# SensorThing.net
KiCad netlist of a schematic drawn in Altium Designer
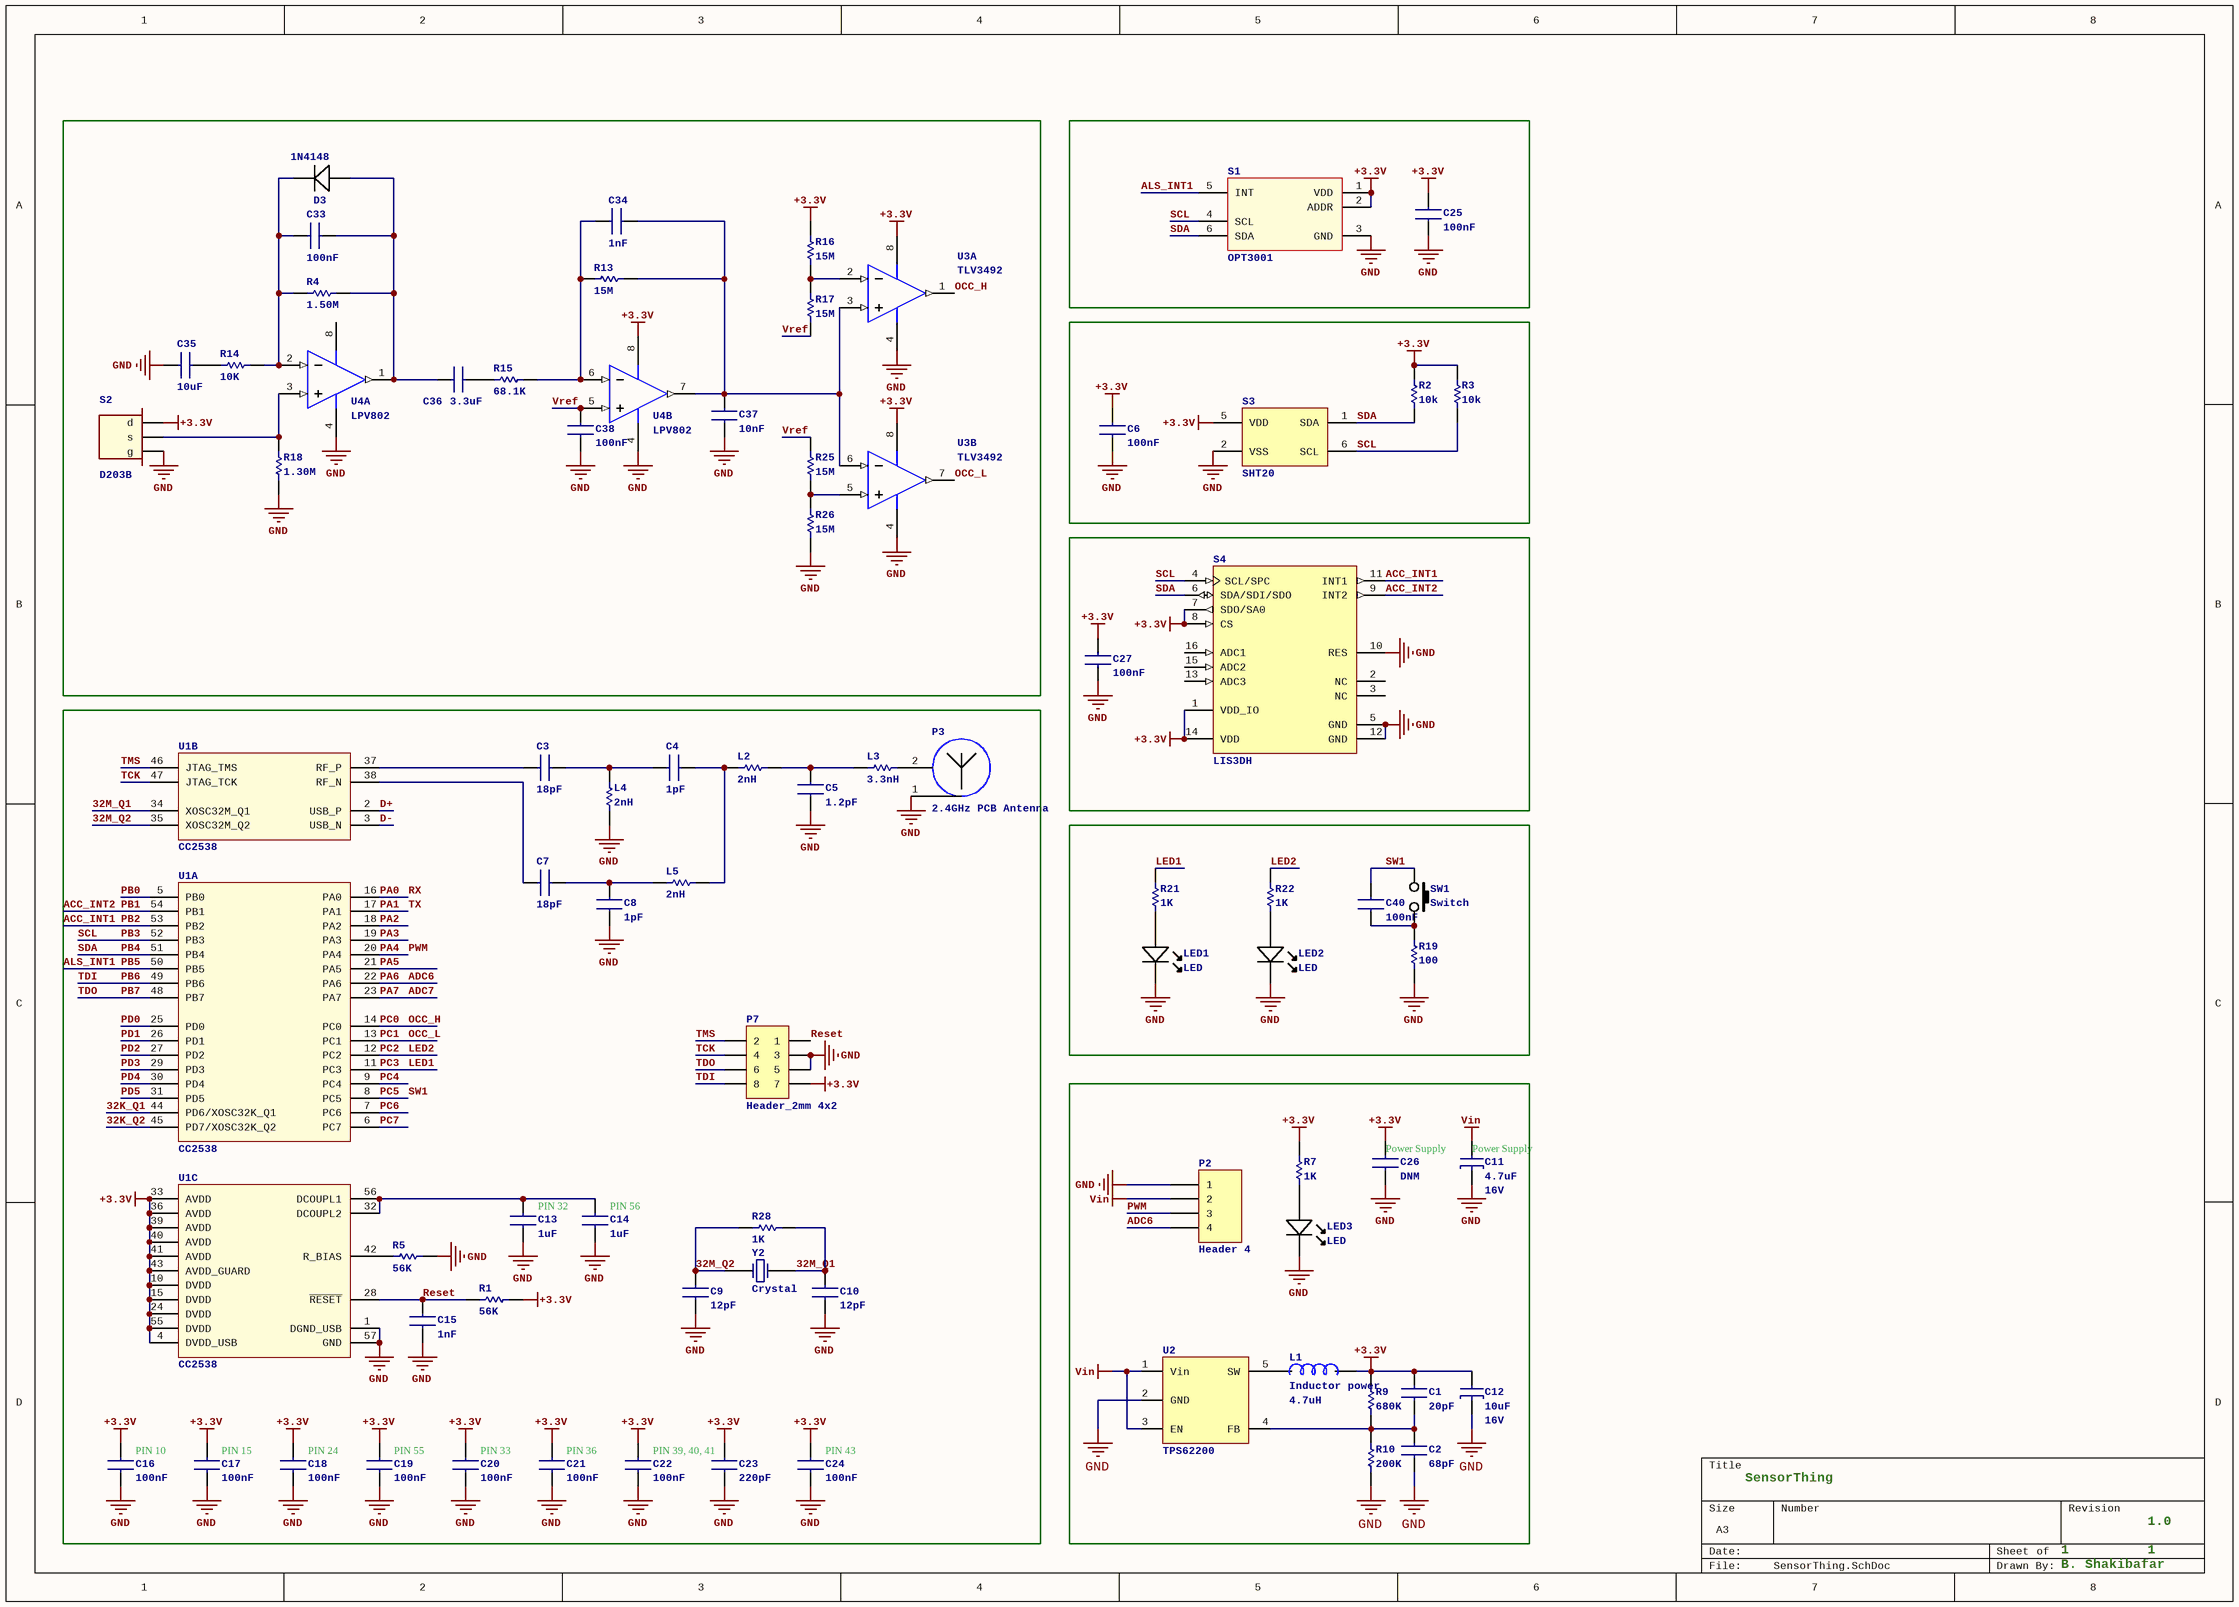
[diagram p0: SensorThing.SchDoc]

(export (version "E")
  (design (tool "Eeschema 10.0.6"))
  (components
    (comp (ref "C1")
      (value "Cap")
      (footprint "CAP 0603")
      (fields (field (name "VOLTAGE") "100V") (field (name "CAPACITY") "20pF"))
      (libsource (lib "Common") (part "Cap"))
    )
    (comp (ref "C2")
      (value "Cap")
      (footprint "CAP 0603")
      (fields (field (name "VOLTAGE") "100V") (field (name "CAPACITY") "68pF"))
      (libsource (lib "Common") (part "Cap"))
    )
    (comp (ref "C3")
      (value "Cap")
      (footprint "CAP 0603")
      (fields (field (name "VOLTAGE") "100V") (field (name "CAPACITY") "18pF"))
      (libsource (lib "Common") (part "Cap"))
    )
    (comp (ref "C4")
      (value "Cap")
      (footprint "CAP 0603")
      (fields (field (name "VOLTAGE") "100V") (field (name "CAPACITY") "1pF"))
      (libsource (lib "Common") (part "Cap"))
    )
    (comp (ref "C5")
      (value "Cap")
      (footprint "CAP 0603")
      (fields (field (name "VOLTAGE") "100V") (field (name "CAPACITY") "1.2pF"))
      (libsource (lib "Common") (part "Cap"))
    )
    (comp (ref "C6")
      (value "Cap")
      (footprint "CAP 0603")
      (fields (field (name "VOLTAGE") "100V") (field (name "CAPACITY") "100nF"))
      (libsource (lib "Common") (part "Cap"))
    )
    (comp (ref "C7")
      (value "Cap")
      (footprint "CAP 0603")
      (fields (field (name "VOLTAGE") "100V") (field (name "CAPACITY") "18pF"))
      (libsource (lib "Common") (part "Cap"))
    )
    (comp (ref "C8")
      (value "Cap")
      (footprint "CAP 0603")
      (fields (field (name "VOLTAGE") "100V") (field (name "CAPACITY") "1pF"))
      (libsource (lib "Common") (part "Cap"))
    )
    (comp (ref "C9")
      (value "Cap")
      (footprint "CAP 0603")
      (fields (field (name "VOLTAGE") "100V") (field (name "CAPACITY") "12pF"))
      (libsource (lib "Common") (part "Cap"))
    )
    (comp (ref "C10")
      (value "Cap")
      (footprint "CAP 0603")
      (fields (field (name "VOLTAGE") "100V") (field (name "CAPACITY") "12pF"))
      (libsource (lib "Common") (part "Cap"))
    )
    (comp (ref "C11")
      (value "Cap pol")
      (footprint "CAP A")
      (fields (field (name "CAPACITY") "4.7uF") (field (name "VOLTAGE") "16V"))
      (libsource (lib "Common") (part "Cap pol"))
    )
    (comp (ref "C12")
      (value "Cap pol")
      (footprint "CAP A")
      (fields (field (name "CAPACITY") "10uF") (field (name "VOLTAGE") "16V"))
      (libsource (lib "Common") (part "Cap pol"))
    )
    (comp (ref "C13")
      (value "Cap")
      (footprint "CAP 0603")
      (fields (field (name "VOLTAGE") "100V") (field (name "CAPACITY") "1uF"))
      (libsource (lib "Common") (part "Cap"))
    )
    (comp (ref "C14")
      (value "Cap")
      (footprint "CAP 0603")
      (fields (field (name "VOLTAGE") "100V") (field (name "CAPACITY") "1uF"))
      (libsource (lib "Common") (part "Cap"))
    )
    (comp (ref "C15")
      (value "Cap")
      (footprint "CAP 0603")
      (fields (field (name "VOLTAGE") "100V") (field (name "CAPACITY") "1nF"))
      (libsource (lib "Common") (part "Cap"))
    )
    (comp (ref "C16")
      (value "Cap")
      (footprint "CAP 0603")
      (fields (field (name "VOLTAGE") "100V") (field (name "CAPACITY") "100nF"))
      (libsource (lib "Common") (part "Cap"))
    )
    (comp (ref "C17")
      (value "Cap")
      (footprint "CAP 0603")
      (fields (field (name "VOLTAGE") "100V") (field (name "CAPACITY") "100nF"))
      (libsource (lib "Common") (part "Cap"))
    )
    (comp (ref "C18")
      (value "Cap")
      (footprint "CAP 0603")
      (fields (field (name "VOLTAGE") "100V") (field (name "CAPACITY") "100nF"))
      (libsource (lib "Common") (part "Cap"))
    )
    (comp (ref "C19")
      (value "Cap")
      (footprint "CAP 0603")
      (fields (field (name "VOLTAGE") "100V") (field (name "CAPACITY") "100nF"))
      (libsource (lib "Common") (part "Cap"))
    )
    (comp (ref "C20")
      (value "Cap")
      (footprint "CAP 0603")
      (fields (field (name "VOLTAGE") "100V") (field (name "CAPACITY") "100nF"))
      (libsource (lib "Common") (part "Cap"))
    )
    (comp (ref "C21")
      (value "Cap")
      (footprint "CAP 0603")
      (fields (field (name "VOLTAGE") "100V") (field (name "CAPACITY") "100nF"))
      (libsource (lib "Common") (part "Cap"))
    )
    (comp (ref "C22")
      (value "Cap")
      (footprint "CAP 0603")
      (fields (field (name "VOLTAGE") "100V") (field (name "CAPACITY") "100nF"))
      (libsource (lib "Common") (part "Cap"))
    )
    (comp (ref "C23")
      (value "Cap")
      (footprint "CAP 0603")
      (fields (field (name "VOLTAGE") "100V") (field (name "CAPACITY") "220pF"))
      (libsource (lib "Common") (part "Cap"))
    )
    (comp (ref "C24")
      (value "Cap")
      (footprint "CAP 0603")
      (fields (field (name "VOLTAGE") "100V") (field (name "CAPACITY") "100nF"))
      (libsource (lib "Common") (part "Cap"))
    )
    (comp (ref "C25")
      (value "Cap")
      (footprint "CAP 0603")
      (fields (field (name "VOLTAGE") "100V") (field (name "CAPACITY") "100nF"))
      (libsource (lib "Common") (part "Cap"))
    )
    (comp (ref "C26")
      (value "Cap")
      (footprint "CAP 0603")
      (fields (field (name "VOLTAGE") "100V") (field (name "CAPACITY") "DNM"))
      (libsource (lib "Common") (part "Cap"))
    )
    (comp (ref "C27")
      (value "Cap")
      (footprint "CAP 0603")
      (fields (field (name "VOLTAGE") "100V") (field (name "CAPACITY") "100nF"))
      (libsource (lib "Common") (part "Cap"))
    )
    (comp (ref "C33")
      (value "Cap")
      (footprint "CAP 0603")
      (fields (field (name "VOLTAGE") "100V") (field (name "CAPACITY") "100nF"))
      (libsource (lib "Common") (part "Cap"))
    )
    (comp (ref "C34")
      (value "Cap")
      (footprint "CAP 0603")
      (fields (field (name "VOLTAGE") "100V") (field (name "CAPACITY") "1nF"))
      (libsource (lib "Common") (part "Cap"))
    )
    (comp (ref "C35")
      (value "Cap")
      (footprint "CAP 0603")
      (fields (field (name "VOLTAGE") "100V") (field (name "CAPACITY") "10uF"))
      (libsource (lib "Common") (part "Cap"))
    )
    (comp (ref "C36")
      (value "Cap")
      (footprint "CAP 0603")
      (fields (field (name "VOLTAGE") "100V") (field (name "CAPACITY") "3.3uF"))
      (libsource (lib "Common") (part "Cap"))
    )
    (comp (ref "C37")
      (value "Cap")
      (footprint "CAP 0603")
      (fields (field (name "VOLTAGE") "100V") (field (name "CAPACITY") "10nF"))
      (libsource (lib "Common") (part "Cap"))
    )
    (comp (ref "C38")
      (value "Cap")
      (footprint "CAP 0603")
      (fields (field (name "VOLTAGE") "100V") (field (name "CAPACITY") "100nF"))
      (libsource (lib "Common") (part "Cap"))
    )
    (comp (ref "C40")
      (value "Cap")
      (footprint "CAP 0603")
      (fields (field (name "VOLTAGE") "100V") (field (name "CAPACITY") "100nF"))
      (libsource (lib "Common") (part "Cap"))
    )
    (comp (ref "D3") (value "1N4148") (footprint "SOD-523") (libsource (lib "Common") (part "Diode")))
    (comp (ref "L1")
      (value "Inductor power")
      (footprint "INDUCTOR 2520")
      (fields (field (name "ALTIUM_VALUE") "4.7uH"))
      (libsource (lib "Common") (part "Inductor power"))
    )
    (comp (ref "L2")
      (value "Res")
      (footprint "RES 0603")
      (description "Resistor")
      (fields (field (name "OHM") "2nH"))
      (libsource (lib "Common") (part "Res"))
    )
    (comp (ref "L3")
      (value "Res")
      (footprint "RES 0603")
      (description "Resistor")
      (fields (field (name "OHM") "3.3nH"))
      (libsource (lib "Common") (part "Res"))
    )
    (comp (ref "L4")
      (value "Res")
      (footprint "RES 0603")
      (description "Resistor")
      (fields (field (name "OHM") "2nH"))
      (libsource (lib "Common") (part "Res"))
    )
    (comp (ref "L5")
      (value "Res")
      (footprint "RES 0603")
      (description "Resistor")
      (fields (field (name "OHM") "2nH"))
      (libsource (lib "Common") (part "Res"))
    )
    (comp (ref "LED1")
      (value "LED")
      (footprint "LED 0603")
      (description "LED SMD")
      (libsource (lib "Common") (part "LED SMD"))
    )
    (comp (ref "LED2")
      (value "LED")
      (footprint "LED 0603")
      (description "LED SMD")
      (libsource (lib "Common") (part "LED SMD"))
    )
    (comp (ref "LED3")
      (value "LED")
      (footprint "LED 0603")
      (description "LED SMD")
      (libsource (lib "Common") (part "LED SMD"))
    )
    (comp (ref "P2")
      (value "Header 4")
      (footprint "HDR1X4")
      (description "Header, 4-Pin")
      (fields (field (name "PUBLISHER") "Altium Limited"))
      (libsource (lib "Miscellaneous Connectors") (part "Header 4"))
    )
    (comp (ref "P3")
      (value "2.4GHz PCB Antenna")
      (footprint "2.4 GHz Inverted F Antenna 1")
      (libsource (lib "My Lib") (part "2.4GHz PCB Antenna"))
    )
    (comp (ref "P7")
      (value "Header_2mm 4x2")
      (footprint "Header_2mm 4x2")
      (libsource (lib "Common") (part "Header_2mm 4x2"))
    )
    (comp (ref "R1")
      (value "Res")
      (footprint "RES 0603")
      (description "Resistor")
      (fields (field (name "OHM") "56K"))
      (libsource (lib "Common") (part "Res"))
    )
    (comp (ref "R2")
      (value "Res")
      (footprint "RES 0603")
      (description "Resistor")
      (fields (field (name "OHM") "10k"))
      (libsource (lib "Common") (part "Res"))
    )
    (comp (ref "R3")
      (value "Res")
      (footprint "RES 0603")
      (description "Resistor")
      (fields (field (name "OHM") "10k"))
      (libsource (lib "Common") (part "Res"))
    )
    (comp (ref "R4")
      (value "Res")
      (footprint "RES 0603")
      (description "Resistor")
      (fields (field (name "OHM") "1.50M"))
      (libsource (lib "Common") (part "Res"))
    )
    (comp (ref "R5")
      (value "Res")
      (footprint "RES 0603")
      (description "Resistor")
      (fields (field (name "OHM") "56K"))
      (libsource (lib "Common") (part "Res"))
    )
    (comp (ref "R7")
      (value "Res")
      (footprint "RES 0603")
      (description "Resistor")
      (fields (field (name "OHM") "1K"))
      (libsource (lib "Common") (part "Res"))
    )
    (comp (ref "R9")
      (value "Res")
      (footprint "RES 0603")
      (description "Resistor")
      (fields (field (name "OHM") "680K"))
      (libsource (lib "Common") (part "Res"))
    )
    (comp (ref "R10")
      (value "Res")
      (footprint "RES 0603")
      (description "Resistor")
      (fields (field (name "OHM") "200K"))
      (libsource (lib "Common") (part "Res"))
    )
    (comp (ref "R13")
      (value "Res")
      (footprint "RES 0603")
      (description "Resistor")
      (fields (field (name "OHM") "15M"))
      (libsource (lib "Common") (part "Res"))
    )
    (comp (ref "R14")
      (value "Res")
      (footprint "RES 0603")
      (description "Resistor")
      (fields (field (name "OHM") "10K"))
      (libsource (lib "Common") (part "Res"))
    )
    (comp (ref "R15")
      (value "Res")
      (footprint "RES 0603")
      (description "Resistor")
      (fields (field (name "OHM") "68.1K"))
      (libsource (lib "Common") (part "Res"))
    )
    (comp (ref "R16")
      (value "Res")
      (footprint "RES 0603")
      (description "Resistor")
      (fields (field (name "OHM") "15M"))
      (libsource (lib "Common") (part "Res"))
    )
    (comp (ref "R17")
      (value "Res")
      (footprint "RES 0603")
      (description "Resistor")
      (fields (field (name "OHM") "15M"))
      (libsource (lib "Common") (part "Res"))
    )
    (comp (ref "R18")
      (value "Res")
      (footprint "RES 0603")
      (description "Resistor")
      (fields (field (name "OHM") "1.30M"))
      (libsource (lib "Common") (part "Res"))
    )
    (comp (ref "R19")
      (value "Res")
      (footprint "RES 0603")
      (description "Resistor")
      (fields (field (name "OHM") "100"))
      (libsource (lib "Common") (part "Res"))
    )
    (comp (ref "R21")
      (value "Res")
      (footprint "RES 0603")
      (description "Resistor")
      (fields (field (name "OHM") "1K"))
      (libsource (lib "Common") (part "Res"))
    )
    (comp (ref "R22")
      (value "Res")
      (footprint "RES 0603")
      (description "Resistor")
      (fields (field (name "OHM") "1K"))
      (libsource (lib "Common") (part "Res"))
    )
    (comp (ref "R25")
      (value "Res")
      (footprint "RES 0603")
      (description "Resistor")
      (fields (field (name "OHM") "15M"))
      (libsource (lib "Common") (part "Res"))
    )
    (comp (ref "R26")
      (value "Res")
      (footprint "RES 0603")
      (description "Resistor")
      (fields (field (name "OHM") "15M"))
      (libsource (lib "Common") (part "Res"))
    )
    (comp (ref "R28")
      (value "Res")
      (footprint "RES 0603")
      (description "Resistor")
      (fields (field (name "OHM") "1K"))
      (libsource (lib "Common") (part "Res"))
    )
    (comp (ref "S1") (value "OPT3001") (footprint "USON-6pin") (libsource (lib "Chips") (part "OPT3001")))
    (comp (ref "S2") (value "D203B") (footprint "D203B") (libsource (lib "Common") (part "D203B PIR sensor")))
    (comp (ref "S3") (value "SHT20") (footprint "SHT20") (libsource (lib "My Lib") (part "SHT20")))
    (comp (ref "S4")
      (value "LIS3DH")
      (footprint "LGA16-3X3X1_N")
      (fields (field (name "MANUFACTURER") "STMicroelectronics"))
      (libsource (lib "STMicroelectronics Sensors & MEMS") (part "LIS3DH"))
    )
    (comp (ref "SW1")
      (value "Switch")
      (footprint "Switch Side-B3U")
      (description "micro Switch")
      (libsource (lib "Common") (part "Switch"))
    )
    (comp (ref "U1") (value "CC2538") (footprint "PVQFN56-CC2538") (libsource (lib "Chips") (part "CC2538")))
    (comp (ref "U2")
      (value "TPS62200")
      (footprint "SOT23-5")
      (description "NAND gate")
      (libsource (lib "My Lib") (part "TPS6220"))
    )
    (comp (ref "U3") (value "TLV3492") (footprint "VSSOP 8-Pin") (libsource (lib "My Lib") (part "TLV3492")))
    (comp (ref "U4") (value "LPV802") (footprint "VSSOP 8-Pin") (libsource (lib "My Lib") (part "LPV802")))
    (comp (ref "Y2") (value "Crystal") (footprint "Crystal 3225") (libsource (lib "Common") (part "Xtal")))
  )
  (nets
    (net (code "1") (name "+3.3V") (class "Default")
      (node (ref "C1") (pin "1") (pinfunction "1_1") (pintype "passive"))
      (node (ref "C12") (pin "1") (pinfunction "1_1") (pintype "passive"))
      (node (ref "C16") (pin "1") (pinfunction "1_1") (pintype "passive"))
      (node (ref "C17") (pin "1") (pinfunction "1_1") (pintype "passive"))
      (node (ref "C18") (pin "1") (pinfunction "1_1") (pintype "passive"))
      (node (ref "C19") (pin "1") (pinfunction "1_1") (pintype "passive"))
      (node (ref "C20") (pin "1") (pinfunction "1_1") (pintype "passive"))
      (node (ref "C21") (pin "1") (pinfunction "1_1") (pintype "passive"))
      (node (ref "C22") (pin "1") (pinfunction "1_1") (pintype "passive"))
      (node (ref "C23") (pin "1") (pinfunction "1_1") (pintype "passive"))
      (node (ref "C24") (pin "1") (pinfunction "1_1") (pintype "passive"))
      (node (ref "C25") (pin "1") (pinfunction "1_1") (pintype "passive"))
      (node (ref "C26") (pin "1") (pinfunction "1_1") (pintype "passive"))
      (node (ref "C27") (pin "1") (pinfunction "1_1") (pintype "passive"))
      (node (ref "C6") (pin "1") (pinfunction "1_1") (pintype "passive"))
      (node (ref "L1") (pin "2") (pinfunction "2_2") (pintype "passive"))
      (node (ref "P7") (pin "7") (pinfunction "7_7") (pintype "passive"))
      (node (ref "R1") (pin "2") (pinfunction "2_2") (pintype "passive"))
      (node (ref "R16") (pin "2") (pinfunction "2_2") (pintype "passive"))
      (node (ref "R2") (pin "1") (pinfunction "1_1") (pintype "passive"))
      (node (ref "R3") (pin "1") (pinfunction "1_1") (pintype "passive"))
      (node (ref "R7") (pin "1") (pinfunction "1_1") (pintype "passive"))
      (node (ref "R9") (pin "1") (pinfunction "1_1") (pintype "passive"))
      (node (ref "S1") (pin "1") (pinfunction "VDD_1") (pintype "power_in"))
      (node (ref "S1") (pin "2") (pinfunction "ADDR_2") (pintype "power_in"))
      (node (ref "S2") (pin "1") (pinfunction "d_1") (pintype "passive"))
      (node (ref "S3") (pin "5") (pinfunction "VDD_5") (pintype "passive"))
      (node (ref "S4") (pin "1") (pinfunction "VDD_IO_1") (pintype "power_in"))
      (node (ref "S4") (pin "14") (pinfunction "VDD_14") (pintype "power_in"))
      (node (ref "S4") (pin "7") (pinfunction "SDO/SA0_7") (pintype "output"))
      (node (ref "S4") (pin "8") (pinfunction "CS_8") (pintype "input"))
      (node (ref "U1") (pin "10") (pinfunction "DVDD_10") (pintype "power_in"))
      (node (ref "U1") (pin "15") (pinfunction "DVDD_15") (pintype "power_in"))
      (node (ref "U1") (pin "24") (pinfunction "DVDD_24") (pintype "power_in"))
      (node (ref "U1") (pin "33") (pinfunction "AVDD_33") (pintype "power_in"))
      (node (ref "U1") (pin "36") (pinfunction "AVDD_36") (pintype "power_in"))
      (node (ref "U1") (pin "39") (pinfunction "AVDD_39") (pintype "power_in"))
      (node (ref "U1") (pin "4") (pinfunction "DVDD_USB_4") (pintype "power_in"))
      (node (ref "U1") (pin "40") (pinfunction "AVDD_40") (pintype "power_in"))
      (node (ref "U1") (pin "41") (pinfunction "AVDD_41") (pintype "power_in"))
      (node (ref "U1") (pin "43") (pinfunction "AVDD_GUARD_43") (pintype "power_in"))
      (node (ref "U1") (pin "55") (pinfunction "DVDD_55") (pintype "power_in"))
      (node (ref "U3") (pin "8") (pinfunction "V+_8") (pintype "power_in"))
      (node (ref "U4") (pin "8") (pinfunction "V+_8") (pintype "power_in"))
    )
    (net (code "2") (name "/32K_Q1") (class "Default")
      (node (ref "U1") (pin "44") (pinfunction "PD6/XOSC32K_Q1_44") (pintype "power_in"))
    )
    (net (code "3") (name "/32K_Q2") (class "Default")
      (node (ref "U1") (pin "45") (pinfunction "PD7/XOSC32K_Q2_45") (pintype "power_in"))
    )
    (net (code "4") (name "/32M_Q1") (class "Default")
      (node (ref "C10") (pin "1") (pinfunction "1_1") (pintype "passive"))
      (node (ref "R28") (pin "2") (pinfunction "2_2") (pintype "passive"))
      (node (ref "U1") (pin "34") (pinfunction "XOSC32M_Q1_34") (pintype "passive"))
      (node (ref "Y2") (pin "2") (pinfunction "2_2") (pintype "passive"))
    )
    (net (code "5") (name "/32M_Q2") (class "Default")
      (node (ref "C9") (pin "1") (pinfunction "1_1") (pintype "passive"))
      (node (ref "R28") (pin "1") (pinfunction "1_1") (pintype "passive"))
      (node (ref "U1") (pin "35") (pinfunction "XOSC32M_Q2_35") (pintype "passive"))
      (node (ref "Y2") (pin "1") (pinfunction "1_1") (pintype "passive"))
    )
    (net (code "6") (name "/ACC_INT1") (class "Default")
      (node (ref "S4") (pin "11") (pinfunction "INT1_11") (pintype "output"))
      (node (ref "U1") (pin "53") (pinfunction "PB2_53") (pintype "power_in"))
    )
    (net (code "7") (name "/ACC_INT2") (class "Default")
      (node (ref "S4") (pin "9") (pinfunction "INT2_9") (pintype "output"))
      (node (ref "U1") (pin "54") (pinfunction "PB1_54") (pintype "power_in"))
    )
    (net (code "8") (name "/ADC6") (class "Default")
      (node (ref "P2") (pin "4") (pinfunction "4_4") (pintype "passive"))
      (node (ref "U1") (pin "22") (pinfunction "PA6_22") (pintype "power_in"))
    )
    (net (code "9") (name "/ADC7") (class "Default")
      (node (ref "U1") (pin "23") (pinfunction "PA7_23") (pintype "power_in"))
    )
    (net (code "10") (name "/ALS_INT1") (class "Default")
      (node (ref "S1") (pin "5") (pinfunction "INT_5") (pintype "power_in"))
      (node (ref "U1") (pin "50") (pinfunction "PB5_50") (pintype "power_in"))
    )
    (net (code "11") (name "/D+") (class "Default")
      (node (ref "U1") (pin "2") (pinfunction "USB_P_2") (pintype "passive"))
    )
    (net (code "12") (name "/D-") (class "Default")
      (node (ref "U1") (pin "3") (pinfunction "USB_N_3") (pintype "passive"))
    )
    (net (code "13") (name "/LED1") (class "Default")
      (node (ref "R21") (pin "1") (pinfunction "1_1") (pintype "passive"))
      (node (ref "U1") (pin "11") (pinfunction "PC3_11") (pintype "power_in"))
    )
    (net (code "14") (name "/LED2") (class "Default")
      (node (ref "R22") (pin "1") (pinfunction "1_1") (pintype "passive"))
      (node (ref "U1") (pin "12") (pinfunction "PC2_12") (pintype "power_in"))
    )
    (net (code "15") (name "/OCC_H") (class "Default")
      (node (ref "U1") (pin "14") (pinfunction "PC0_14") (pintype "power_in"))
      (node (ref "U3") (pin "1") (pinfunction "1_1") (pintype "output"))
    )
    (net (code "16") (name "/OCC_L") (class "Default")
      (node (ref "U1") (pin "13") (pinfunction "PC1_13") (pintype "power_in"))
      (node (ref "U3") (pin "7") (pinfunction "7_7") (pintype "output"))
    )
    (net (code "17") (name "/PA0") (class "Default")
      (node (ref "U1") (pin "16") (pinfunction "PA0_16") (pintype "power_in"))
    )
    (net (code "18") (name "/PA1") (class "Default")
      (node (ref "U1") (pin "17") (pinfunction "PA1_17") (pintype "power_in"))
    )
    (net (code "19") (name "/PA2") (class "Default")
      (node (ref "U1") (pin "18") (pinfunction "PA2_18") (pintype "power_in"))
    )
    (net (code "20") (name "/PA3") (class "Default")
      (node (ref "U1") (pin "19") (pinfunction "PA3_19") (pintype "power_in"))
    )
    (net (code "21") (name "/PA4") (class "Default")
      (node (ref "P2") (pin "3") (pinfunction "3_3") (pintype "passive"))
      (node (ref "U1") (pin "20") (pinfunction "PA4_20") (pintype "power_in"))
    )
    (net (code "22") (name "/PA5") (class "Default")
      (node (ref "U1") (pin "21") (pinfunction "PA5_21") (pintype "power_in"))
    )
    (net (code "23") (name "/PB0") (class "Default")
      (node (ref "U1") (pin "5") (pinfunction "PB0_5") (pintype "power_in"))
    )
    (net (code "24") (name "/PB3") (class "Default")
      (node (ref "R3") (pin "2") (pinfunction "2_2") (pintype "passive"))
      (node (ref "S1") (pin "4") (pinfunction "SCL_4") (pintype "power_in"))
      (node (ref "S3") (pin "6") (pinfunction "SCL_6") (pintype "passive"))
      (node (ref "S4") (pin "4") (pinfunction "SCL/SPC_4") (pintype "input"))
      (node (ref "U1") (pin "52") (pinfunction "PB3_52") (pintype "power_in"))
    )
    (net (code "25") (name "/PB4") (class "Default")
      (node (ref "R2") (pin "2") (pinfunction "2_2") (pintype "passive"))
      (node (ref "S1") (pin "6") (pinfunction "SDA_6") (pintype "power_in"))
      (node (ref "S3") (pin "1") (pinfunction "SDA_1") (pintype "passive"))
      (node (ref "S4") (pin "6") (pinfunction "SDA/SDI/SDO_6") (pintype "bidirectional"))
      (node (ref "U1") (pin "51") (pinfunction "PB4_51") (pintype "power_in"))
    )
    (net (code "26") (name "/PB6") (class "Default")
      (node (ref "P7") (pin "8") (pinfunction "8_8") (pintype "passive"))
      (node (ref "U1") (pin "49") (pinfunction "PB6_49") (pintype "power_in"))
    )
    (net (code "27") (name "/PB7") (class "Default")
      (node (ref "P7") (pin "6") (pinfunction "6_6") (pintype "passive"))
      (node (ref "U1") (pin "48") (pinfunction "PB7_48") (pintype "power_in"))
    )
    (net (code "28") (name "/PC4") (class "Default")
      (node (ref "U1") (pin "9") (pinfunction "PC4_9") (pintype "power_in"))
    )
    (net (code "29") (name "/PC5") (class "Default")
      (node (ref "C40") (pin "1") (pinfunction "1_1") (pintype "passive"))
      (node (ref "SW1") (pin "1") (pintype "passive"))
      (node (ref "U1") (pin "8") (pinfunction "PC5_8") (pintype "power_in"))
    )
    (net (code "30") (name "/PC6") (class "Default")
      (node (ref "U1") (pin "7") (pinfunction "PC6_7") (pintype "power_in"))
    )
    (net (code "31") (name "/PC7") (class "Default")
      (node (ref "U1") (pin "6") (pinfunction "PC7_6") (pintype "power_in"))
    )
    (net (code "32") (name "/PD0") (class "Default")
      (node (ref "U1") (pin "25") (pinfunction "PD0_25") (pintype "power_in"))
    )
    (net (code "33") (name "/PD1") (class "Default")
      (node (ref "U1") (pin "26") (pinfunction "PD1_26") (pintype "power_in"))
    )
    (net (code "34") (name "/PD2") (class "Default")
      (node (ref "U1") (pin "27") (pinfunction "PD2_27") (pintype "power_in"))
    )
    (net (code "35") (name "/PD3") (class "Default")
      (node (ref "U1") (pin "29") (pinfunction "PD3_29") (pintype "power_in"))
    )
    (net (code "36") (name "/PD4") (class "Default")
      (node (ref "U1") (pin "30") (pinfunction "PD4_30") (pintype "power_in"))
    )
    (net (code "37") (name "/PD5") (class "Default")
      (node (ref "U1") (pin "31") (pinfunction "PD5_31") (pintype "power_in"))
    )
    (net (code "38") (name "/Reset") (class "Default")
      (node (ref "C15") (pin "1") (pinfunction "1_1") (pintype "passive"))
      (node (ref "P7") (pin "1") (pinfunction "1_1") (pintype "passive"))
      (node (ref "R1") (pin "1") (pinfunction "1_1") (pintype "passive"))
      (node (ref "U1") (pin "28") (pinfunction "~{RESET}_28") (pintype "power_in"))
    )
    (net (code "39") (name "/TCK") (class "Default")
      (node (ref "P7") (pin "4") (pinfunction "4_4") (pintype "passive"))
      (node (ref "U1") (pin "47") (pinfunction "JTAG_TCK_47") (pintype "power_in"))
    )
    (net (code "40") (name "/TMS") (class "Default")
      (node (ref "P7") (pin "2") (pinfunction "2_2") (pintype "passive"))
      (node (ref "U1") (pin "46") (pinfunction "JTAG_TMS_46") (pintype "power_in"))
    )
    (net (code "41") (name "/Vref") (class "Default")
      (node (ref "C38") (pin "1") (pinfunction "1_1") (pintype "passive"))
      (node (ref "R17") (pin "1") (pinfunction "1_1") (pintype "passive"))
      (node (ref "R25") (pin "2") (pinfunction "2_2") (pintype "passive"))
      (node (ref "U4") (pin "5") (pinfunction "5_5") (pintype "input"))
    )
    (net (code "42") (name "GND") (class "Default")
      (node (ref "C10") (pin "2") (pinfunction "2_2") (pintype "passive"))
      (node (ref "C11") (pin "2") (pinfunction "2_2") (pintype "passive"))
      (node (ref "C12") (pin "2") (pinfunction "2_2") (pintype "passive"))
      (node (ref "C13") (pin "2") (pinfunction "2_2") (pintype "passive"))
      (node (ref "C14") (pin "2") (pinfunction "2_2") (pintype "passive"))
      (node (ref "C15") (pin "2") (pinfunction "2_2") (pintype "passive"))
      (node (ref "C16") (pin "2") (pinfunction "2_2") (pintype "passive"))
      (node (ref "C17") (pin "2") (pinfunction "2_2") (pintype "passive"))
      (node (ref "C18") (pin "2") (pinfunction "2_2") (pintype "passive"))
      (node (ref "C19") (pin "2") (pinfunction "2_2") (pintype "passive"))
      (node (ref "C2") (pin "2") (pinfunction "2_2") (pintype "passive"))
      (node (ref "C20") (pin "2") (pinfunction "2_2") (pintype "passive"))
      (node (ref "C21") (pin "2") (pinfunction "2_2") (pintype "passive"))
      (node (ref "C22") (pin "2") (pinfunction "2_2") (pintype "passive"))
      (node (ref "C23") (pin "2") (pinfunction "2_2") (pintype "passive"))
      (node (ref "C24") (pin "2") (pinfunction "2_2") (pintype "passive"))
      (node (ref "C25") (pin "2") (pinfunction "2_2") (pintype "passive"))
      (node (ref "C26") (pin "2") (pinfunction "2_2") (pintype "passive"))
      (node (ref "C27") (pin "2") (pinfunction "2_2") (pintype "passive"))
      (node (ref "C35") (pin "2") (pinfunction "2_2") (pintype "passive"))
      (node (ref "C37") (pin "2") (pinfunction "2_2") (pintype "passive"))
      (node (ref "C38") (pin "2") (pinfunction "2_2") (pintype "passive"))
      (node (ref "C5") (pin "2") (pinfunction "2_2") (pintype "passive"))
      (node (ref "C6") (pin "2") (pinfunction "2_2") (pintype "passive"))
      (node (ref "C8") (pin "2") (pinfunction "2_2") (pintype "passive"))
      (node (ref "C9") (pin "2") (pinfunction "2_2") (pintype "passive"))
      (node (ref "L4") (pin "1") (pinfunction "1_1") (pintype "passive"))
      (node (ref "LED1") (pin "2") (pinfunction "2_2") (pintype "passive"))
      (node (ref "LED2") (pin "2") (pinfunction "2_2") (pintype "passive"))
      (node (ref "LED3") (pin "2") (pinfunction "2_2") (pintype "passive"))
      (node (ref "P2") (pin "1") (pinfunction "1_1") (pintype "passive"))
      (node (ref "P3") (pin "1") (pintype "passive"))
      (node (ref "P7") (pin "3") (pinfunction "3_3") (pintype "passive"))
      (node (ref "P7") (pin "5") (pinfunction "5_5") (pintype "passive"))
      (node (ref "R10") (pin "2") (pinfunction "2_2") (pintype "passive"))
      (node (ref "R18") (pin "1") (pinfunction "1_1") (pintype "passive"))
      (node (ref "R19") (pin "2") (pinfunction "2_2") (pintype "passive"))
      (node (ref "R26") (pin "1") (pinfunction "1_1") (pintype "passive"))
      (node (ref "R5") (pin "2") (pinfunction "2_2") (pintype "passive"))
      (node (ref "S1") (pin "3") (pinfunction "GND_3") (pintype "power_in"))
      (node (ref "S2") (pin "3") (pinfunction "g_3") (pintype "passive"))
      (node (ref "S3") (pin "2") (pinfunction "VSS_2") (pintype "passive"))
      (node (ref "S4") (pin "10") (pinfunction "RES_10") (pintype "passive"))
      (node (ref "S4") (pin "12") (pinfunction "GND_12") (pintype "power_in"))
      (node (ref "S4") (pin "5") (pinfunction "GND_5") (pintype "power_in"))
      (node (ref "U1") (pin "1") (pinfunction "DGND_USB_1") (pintype "power_in"))
      (node (ref "U1") (pin "57") (pinfunction "GND_57") (pintype "power_in"))
      (node (ref "U2") (pin "2") (pinfunction "GND_2") (pintype "passive"))
      (node (ref "U3") (pin "4") (pinfunction "4_4") (pintype "power_in"))
      (node (ref "U4") (pin "4") (pinfunction "4_4") (pintype "power_in"))
    )
    (net (code "43") (name "Net-(C3-Pad1)") (class "Default")
      (node (ref "C3") (pin "1") (pinfunction "1_1") (pintype "passive"))
      (node (ref "C4") (pin "2") (pinfunction "2_2") (pintype "passive"))
      (node (ref "L4") (pin "2") (pinfunction "2_2") (pintype "passive"))
    )
    (net (code "44") (name "Net-(C4-Pad1)") (class "Default")
      (node (ref "C4") (pin "1") (pinfunction "1_1") (pintype "passive"))
      (node (ref "L2") (pin "2") (pinfunction "2_2") (pintype "passive"))
      (node (ref "L5") (pin "1") (pinfunction "1_1") (pintype "passive"))
    )
    (net (code "45") (name "Net-(C5-Pad1)") (class "Default")
      (node (ref "C5") (pin "1") (pinfunction "1_1") (pintype "passive"))
      (node (ref "L2") (pin "1") (pinfunction "1_1") (pintype "passive"))
      (node (ref "L3") (pin "2") (pinfunction "2_2") (pintype "passive"))
    )
    (net (code "46") (name "Net-(C7-Pad1)") (class "Default")
      (node (ref "C7") (pin "1") (pinfunction "1_1") (pintype "passive"))
      (node (ref "C8") (pin "1") (pinfunction "1_1") (pintype "passive"))
      (node (ref "L5") (pin "2") (pinfunction "2_2") (pintype "passive"))
    )
    (net (code "47") (name "Net-(C33-Pad1)") (class "Default")
      (node (ref "C33") (pin "1") (pinfunction "1_1") (pintype "passive"))
      (node (ref "D3") (pin "2") (pinfunction "2_2") (pintype "passive"))
      (node (ref "R14") (pin "2") (pinfunction "2_2") (pintype "passive"))
      (node (ref "R4") (pin "1") (pinfunction "1_1") (pintype "passive"))
      (node (ref "U4") (pin "2") (pinfunction "2_2") (pintype "input"))
    )
    (net (code "48") (name "Net-(C33-Pad2)") (class "Default")
      (node (ref "C33") (pin "2") (pinfunction "2_2") (pintype "passive"))
      (node (ref "C36") (pin "2") (pinfunction "2_2") (pintype "passive"))
      (node (ref "D3") (pin "1") (pinfunction "1_1") (pintype "passive"))
      (node (ref "R4") (pin "2") (pinfunction "2_2") (pintype "passive"))
      (node (ref "U4") (pin "1") (pinfunction "1_1") (pintype "output"))
    )
    (net (code "49") (name "Net-(C34-Pad1)") (class "Default")
      (node (ref "C34") (pin "1") (pinfunction "1_1") (pintype "passive"))
      (node (ref "R13") (pin "1") (pinfunction "1_1") (pintype "passive"))
      (node (ref "R15") (pin "2") (pinfunction "2_2") (pintype "passive"))
      (node (ref "U4") (pin "6") (pinfunction "6_6") (pintype "input"))
    )
    (net (code "50") (name "Net-(C34-Pad2)") (class "Default")
      (node (ref "C34") (pin "2") (pinfunction "2_2") (pintype "passive"))
      (node (ref "C37") (pin "1") (pinfunction "1_1") (pintype "passive"))
      (node (ref "R13") (pin "2") (pinfunction "2_2") (pintype "passive"))
      (node (ref "U3") (pin "3") (pinfunction "3_3") (pintype "input"))
      (node (ref "U3") (pin "6") (pinfunction "6_6") (pintype "input"))
      (node (ref "U4") (pin "7") (pinfunction "7_7") (pintype "output"))
    )
    (net (code "51") (name "Net-(C35-Pad1)") (class "Default")
      (node (ref "C35") (pin "1") (pinfunction "1_1") (pintype "passive"))
      (node (ref "R14") (pin "1") (pinfunction "1_1") (pintype "passive"))
    )
    (net (code "52") (name "Net-(C36-Pad1)") (class "Default")
      (node (ref "C36") (pin "1") (pinfunction "1_1") (pintype "passive"))
      (node (ref "R15") (pin "1") (pinfunction "1_1") (pintype "passive"))
    )
    (net (code "53") (name "Net-(C40-Pad2)") (class "Default")
      (node (ref "C40") (pin "2") (pinfunction "2_2") (pintype "passive"))
      (node (ref "R19") (pin "1") (pinfunction "1_1") (pintype "passive"))
      (node (ref "SW1") (pin "2") (pintype "passive"))
    )
    (net (code "54") (name "Net-(L3-Pad1)") (class "Default")
      (node (ref "L3") (pin "1") (pinfunction "1_1") (pintype "passive"))
      (node (ref "P3") (pin "2") (pintype "passive"))
    )
    (net (code "55") (name "Net-(LED1-Pad1)") (class "Default")
      (node (ref "LED1") (pin "1") (pinfunction "1_1") (pintype "passive"))
      (node (ref "R21") (pin "2") (pinfunction "2_2") (pintype "passive"))
    )
    (net (code "56") (name "Net-(LED2-Pad1)") (class "Default")
      (node (ref "LED2") (pin "1") (pinfunction "1_1") (pintype "passive"))
      (node (ref "R22") (pin "2") (pinfunction "2_2") (pintype "passive"))
    )
    (net (code "57") (name "Net-(LED3-Pad1)") (class "Default")
      (node (ref "LED3") (pin "1") (pinfunction "1_1") (pintype "passive"))
      (node (ref "R7") (pin "2") (pinfunction "2_2") (pintype "passive"))
    )
    (net (code "58") (name "Net-(R16-Pad1)") (class "Default")
      (node (ref "R16") (pin "1") (pinfunction "1_1") (pintype "passive"))
      (node (ref "R17") (pin "2") (pinfunction "2_2") (pintype "passive"))
      (node (ref "U3") (pin "2") (pinfunction "2_2") (pintype "input"))
    )
    (net (code "59") (name "Net-(R25-Pad1)") (class "Default")
      (node (ref "R25") (pin "1") (pinfunction "1_1") (pintype "passive"))
      (node (ref "R26") (pin "2") (pinfunction "2_2") (pintype "passive"))
      (node (ref "U3") (pin "5") (pinfunction "5_5") (pintype "input"))
    )
    (net (code "60") (name "Net-(S2-s)") (class "Default")
      (node (ref "R18") (pin "2") (pinfunction "2_2") (pintype "passive"))
      (node (ref "S2") (pin "2") (pinfunction "s_2") (pintype "passive"))
      (node (ref "U4") (pin "3") (pinfunction "3_3") (pintype "input"))
    )
    (net (code "61") (name "Net-(U1B-RF_N)") (class "Default")
      (node (ref "C7") (pin "2") (pinfunction "2_2") (pintype "passive"))
      (node (ref "U1") (pin "38") (pinfunction "RF_N_38") (pintype "passive"))
    )
    (net (code "62") (name "Net-(U1B-RF_P)") (class "Default")
      (node (ref "C3") (pin "2") (pinfunction "2_2") (pintype "passive"))
      (node (ref "U1") (pin "37") (pinfunction "RF_P_37") (pintype "passive"))
    )
    (net (code "63") (name "Net-(U1C-DCOUPL1)") (class "Default")
      (node (ref "C13") (pin "1") (pinfunction "1_1") (pintype "passive"))
      (node (ref "C14") (pin "1") (pinfunction "1_1") (pintype "passive"))
      (node (ref "U1") (pin "32") (pinfunction "DCOUPL2_32") (pintype "power_in"))
      (node (ref "U1") (pin "56") (pinfunction "DCOUPL1_56") (pintype "power_in"))
    )
    (net (code "64") (name "Net-(U1C-R_BIAS)") (class "Default")
      (node (ref "R5") (pin "1") (pinfunction "1_1") (pintype "passive"))
      (node (ref "U1") (pin "42") (pinfunction "R_BIAS_42") (pintype "passive"))
    )
    (net (code "65") (name "Net-(U2-FB)") (class "Default")
      (node (ref "C1") (pin "2") (pinfunction "2_2") (pintype "passive"))
      (node (ref "C2") (pin "1") (pinfunction "1_1") (pintype "passive"))
      (node (ref "R10") (pin "1") (pinfunction "1_1") (pintype "passive"))
      (node (ref "R9") (pin "2") (pinfunction "2_2") (pintype "passive"))
      (node (ref "U2") (pin "4") (pinfunction "FB_4") (pintype "passive"))
    )
    (net (code "66") (name "Net-(U2-SW)") (class "Default")
      (node (ref "L1") (pin "1") (pinfunction "1_1") (pintype "passive"))
      (node (ref "U2") (pin "5") (pinfunction "SW_5") (pintype "passive"))
    )
    (net (code "67") (name "Vin") (class "Default")
      (node (ref "C11") (pin "1") (pinfunction "1_1") (pintype "passive"))
      (node (ref "P2") (pin "2") (pinfunction "2_2") (pintype "passive"))
      (node (ref "U2") (pin "1") (pinfunction "Vin_1") (pintype "passive"))
      (node (ref "U2") (pin "3") (pinfunction "EN_3") (pintype "passive"))
    )
    (net (code "68") (name "unconnected-(S4-ADC1-Pad16)") (class "Default")
      (node (ref "S4") (pin "16") (pinfunction "ADC1_16") (pintype "input"))
    )
    (net (code "69") (name "unconnected-(S4-ADC2-Pad15)") (class "Default")
      (node (ref "S4") (pin "15") (pinfunction "ADC2_15") (pintype "input"))
    )
    (net (code "70") (name "unconnected-(S4-ADC3-Pad13)") (class "Default")
      (node (ref "S4") (pin "13") (pinfunction "ADC3_13") (pintype "input"))
    )
    (net (code "71") (name "unconnected-(S4-NC-Pad2)") (class "Default")
      (node (ref "S4") (pin "2") (pinfunction "NC_2") (pintype "passive"))
    )
    (net (code "72") (name "unconnected-(S4-NC-Pad3)") (class "Default")
      (node (ref "S4") (pin "3") (pinfunction "NC_3") (pintype "passive"))
    )
    (net (code "73") (name "unconnected-(U4A-V+-Pad8)") (class "Default")
      (node (ref "U4") (pin "8") (pinfunction "V+_8") (pintype "power_in"))
    )
  )
)
